# ManualBot_Shield.net
KiCad netlist of a schematic drawn in EAGLE
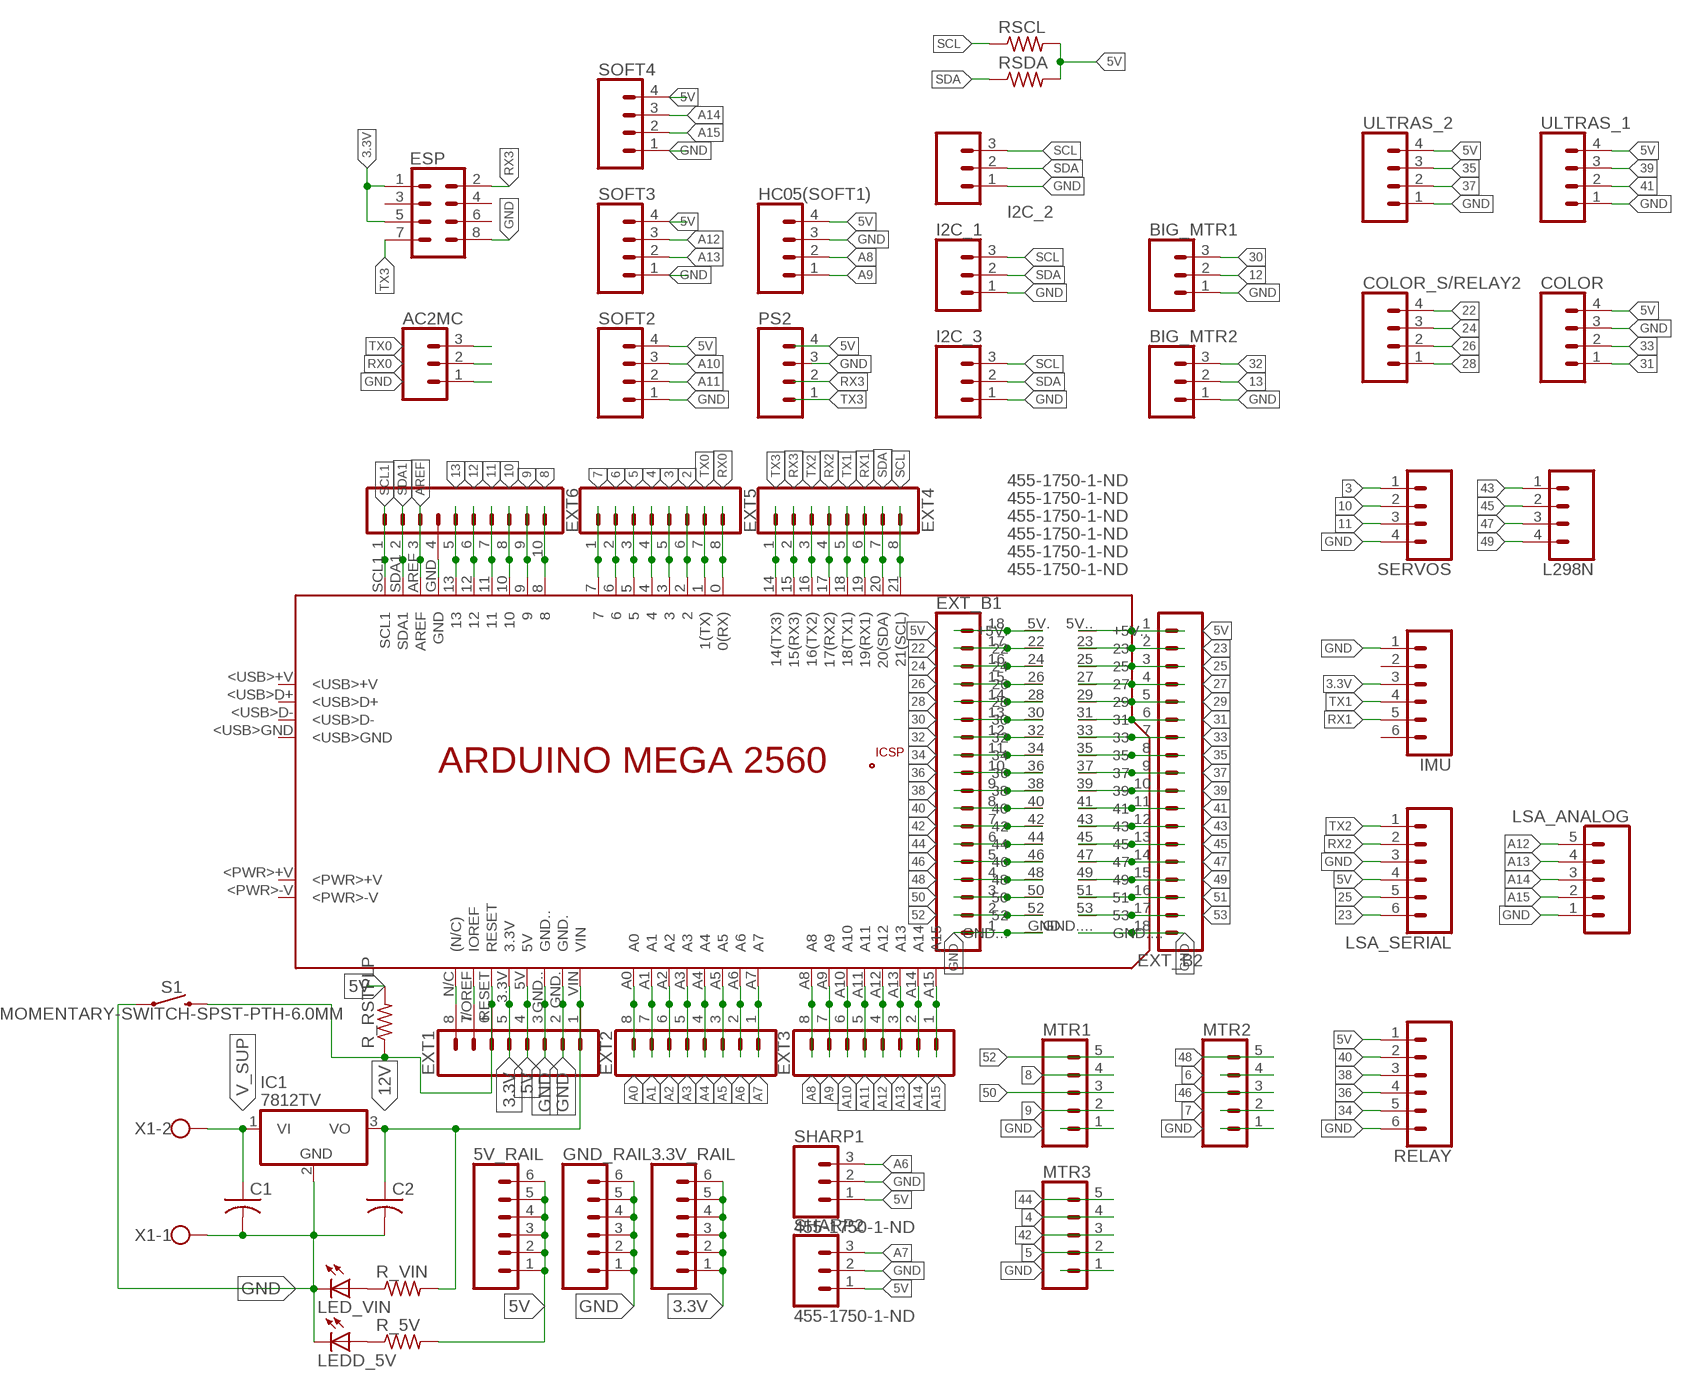
[diagram p0: schematic, sheet 1]

(export (version "E")
  (design (tool "Eeschema 10.0.6"))
  (components
    (comp (ref "3.3V_RAIL")
      (value "CONN_06SILK_FEMALE_PTH")
      (footprint "eagle-import:1X06")
      (libsource (lib "eagle-import") (part "CONN_06SILK_FEMALE_PTH"))
    )
    (comp (ref "5V_RAIL")
      (value "CONN_06SILK_FEMALE_PTH")
      (footprint "eagle-import:1X06")
      (libsource (lib "eagle-import") (part "CONN_06SILK_FEMALE_PTH"))
    )
    (comp (ref "AC2MC")
      (value "455-1750-1-ND")
      (footprint "eagle-import:1X03")
      (libsource (lib "eagle-import") (part "CONN_03"))
    )
    (comp (ref "BIG_MTR1")
      (value "455-1750-1-ND")
      (footprint "eagle-import:1X03")
      (libsource (lib "eagle-import") (part "CONN_03"))
    )
    (comp (ref "BIG_MTR2")
      (value "455-1750-1-ND")
      (footprint "eagle-import:1X03")
      (libsource (lib "eagle-import") (part "CONN_03"))
    )
    (comp (ref "C1")
      (value "C-US025-024X044")
      (footprint "eagle-import:C025-024X044")
      (libsource (lib "eagle-import") (part "C-US025-024X044"))
    )
    (comp (ref "C2")
      (value "C-US025-024X044")
      (footprint "eagle-import:C025-024X044")
      (libsource (lib "eagle-import") (part "C-US025-024X044"))
    )
    (comp (ref "COLOR")
      (value "CONN_04")
      (footprint "eagle-import:1X04")
      (libsource (lib "eagle-import") (part "CONN_04"))
    )
    (comp (ref "COLOR_S/RELAY2")
      (value "CONN_04")
      (footprint "eagle-import:1X04")
      (libsource (lib "eagle-import") (part "CONN_04"))
    )
    (comp (ref "ESP")
      (value "CONN_04X2")
      (footprint "eagle-import:2X4")
      (libsource (lib "eagle-import") (part "CONN_04X2"))
    )
    (comp (ref "EXT1")
      (value "CONN_08\"")
      (footprint "eagle-import:1X08")
      (libsource (lib "eagle-import") (part "CONN_08{dblquote}"))
    )
    (comp (ref "EXT2")
      (value "CONN_08\"")
      (footprint "eagle-import:1X08")
      (libsource (lib "eagle-import") (part "CONN_08{dblquote}"))
    )
    (comp (ref "EXT3")
      (value "CONN_08\"")
      (footprint "eagle-import:1X08")
      (libsource (lib "eagle-import") (part "CONN_08{dblquote}"))
    )
    (comp (ref "EXT4")
      (value "CONN_08\"")
      (footprint "eagle-import:1X08")
      (libsource (lib "eagle-import") (part "CONN_08{dblquote}"))
    )
    (comp (ref "EXT5")
      (value "CONN_08\"")
      (footprint "eagle-import:1X08")
      (libsource (lib "eagle-import") (part "CONN_08{dblquote}"))
    )
    (comp (ref "EXT6")
      (value "CONN_10\"")
      (footprint "eagle-import:1X10")
      (libsource (lib "eagle-import") (part "CONN_10{dblquote}"))
    )
    (comp (ref "EXT_B1")
      (value "CONN_18")
      (footprint "eagle-import:1X18_NO_SILK")
      (libsource (lib "eagle-import") (part "CONN_18"))
    )
    (comp (ref "EXT_B2")
      (value "CONN_18")
      (footprint "eagle-import:1X18_NO_SILK")
      (libsource (lib "eagle-import") (part "CONN_18"))
    )
    (comp (ref "GND_RAIL")
      (value "CONN_06SILK_FEMALE_PTH")
      (footprint "eagle-import:1X06")
      (libsource (lib "eagle-import") (part "CONN_06SILK_FEMALE_PTH"))
    )
    (comp (ref "HC05(SOFT1)")
      (value "CONN_04")
      (footprint "eagle-import:1X04")
      (libsource (lib "eagle-import") (part "CONN_04"))
    )
    (comp (ref "I2C_1")
      (value "455-1750-1-ND")
      (footprint "eagle-import:1X03")
      (libsource (lib "eagle-import") (part "CONN_03"))
    )
    (comp (ref "I2C_2")
      (value "455-1750-1-ND")
      (footprint "eagle-import:1X03")
      (libsource (lib "eagle-import") (part "CONN_03"))
    )
    (comp (ref "I2C_3")
      (value "455-1750-1-ND")
      (footprint "eagle-import:1X03")
      (libsource (lib "eagle-import") (part "CONN_03"))
    )
    (comp (ref "IC1")
      (value "7812TV")
      (footprint "eagle-import:TO220V")
      (libsource (lib "eagle-import") (part "78TV12"))
    )
    (comp (ref "IMU")
      (value "CONN_06SILK_FEMALE_PTH")
      (footprint "eagle-import:1X06")
      (libsource (lib "eagle-import") (part "CONN_06SILK_FEMALE_PTH"))
    )
    (comp (ref "L298N")
      (value "CONN_04")
      (footprint "eagle-import:1X04")
      (libsource (lib "eagle-import") (part "CONN_04"))
    )
    (comp (ref "LEDD_5V")
      (value "LED5MM")
      (footprint "eagle-import:LED5MM")
      (libsource (lib "eagle-import") (part "LED5MM"))
    )
    (comp (ref "LED_VIN")
      (value "LED5MM")
      (footprint "eagle-import:LED5MM")
      (libsource (lib "eagle-import") (part "LED5MM"))
    )
    (comp (ref "LSA_ANALOG")
      (value "CONN_05")
      (footprint "eagle-import:1X05")
      (libsource (lib "eagle-import") (part "CONN_05"))
    )
    (comp (ref "LSA_SERIAL")
      (value "CONN_06SILK_FEMALE_PTH")
      (footprint "eagle-import:1X06")
      (libsource (lib "eagle-import") (part "CONN_06SILK_FEMALE_PTH"))
    )
    (comp (ref "MTR1")
      (value "CONN_05")
      (footprint "eagle-import:1X05")
      (libsource (lib "eagle-import") (part "CONN_05"))
    )
    (comp (ref "MTR2")
      (value "CONN_05")
      (footprint "eagle-import:1X05")
      (libsource (lib "eagle-import") (part "CONN_05"))
    )
    (comp (ref "MTR3")
      (value "CONN_05")
      (footprint "eagle-import:1X05")
      (libsource (lib "eagle-import") (part "CONN_05"))
    )
    (comp (ref "PCB1")
      (value "ARDUINO_MEGA2560")
      (footprint "eagle-import:ARDUINO_MEGA2560")
      (libsource (lib "eagle-import") (part "ARDUINO_MEGA2560"))
    )
    (comp (ref "PS2")
      (value "CONN_04")
      (footprint "eagle-import:1X04")
      (libsource (lib "eagle-import") (part "CONN_04"))
    )
    (comp (ref "RELAY")
      (value "CONN_06SILK_FEMALE_PTH")
      (footprint "eagle-import:1X06")
      (libsource (lib "eagle-import") (part "CONN_06SILK_FEMALE_PTH"))
    )
    (comp (ref "RSCL")
      (value "R-US_0204/7")
      (footprint "eagle-import:0204_7")
      (libsource (lib "eagle-import") (part "R-US_0204/7"))
    )
    (comp (ref "RSDA")
      (value "R-US_0204/7")
      (footprint "eagle-import:0204_7")
      (libsource (lib "eagle-import") (part "R-US_0204/7"))
    )
    (comp (ref "R_5V")
      (value "R-US_0204/7")
      (footprint "eagle-import:0204_7")
      (libsource (lib "eagle-import") (part "R-US_0204/7"))
    )
    (comp (ref "R_RSTPLP")
      (value "R-US_0204/7")
      (footprint "eagle-import:0204_7")
      (libsource (lib "eagle-import") (part "R-US_0204/7"))
    )
    (comp (ref "R_VIN")
      (value "R-US_0204/7")
      (footprint "eagle-import:0204_7")
      (libsource (lib "eagle-import") (part "R-US_0204/7"))
    )
    (comp (ref "S1")
      (value "MOMENTARY-SWITCH-SPST-PTH-6.0MM")
      (footprint "eagle-import:TACTILE_SWITCH_PTH_6.0MM")
      (libsource (lib "eagle-import") (part "MOMENTARY-SWITCH-SPST-PTH-6.0MM"))
    )
    (comp (ref "SERVOS")
      (value "CONN_04")
      (footprint "eagle-import:1X04")
      (libsource (lib "eagle-import") (part "CONN_04"))
    )
    (comp (ref "SHARP1")
      (value "455-1750-1-ND")
      (footprint "eagle-import:1X03")
      (libsource (lib "eagle-import") (part "CONN_03"))
    )
    (comp (ref "SHARP2")
      (value "455-1750-1-ND")
      (footprint "eagle-import:1X03")
      (libsource (lib "eagle-import") (part "CONN_03"))
    )
    (comp (ref "SOFT2")
      (value "CONN_04")
      (footprint "eagle-import:1X04")
      (libsource (lib "eagle-import") (part "CONN_04"))
    )
    (comp (ref "SOFT3")
      (value "CONN_04")
      (footprint "eagle-import:1X04")
      (libsource (lib "eagle-import") (part "CONN_04"))
    )
    (comp (ref "SOFT4")
      (value "CONN_04")
      (footprint "eagle-import:1X04")
      (libsource (lib "eagle-import") (part "CONN_04"))
    )
    (comp (ref "ULTRAS_1")
      (value "CONN_04")
      (footprint "eagle-import:1X04")
      (libsource (lib "eagle-import") (part "CONN_04"))
    )
    (comp (ref "ULTRAS_2")
      (value "CONN_04")
      (footprint "eagle-import:1X04")
      (libsource (lib "eagle-import") (part "CONN_04"))
    )
    (comp (ref "X1")
      (value "W237-102")
      (footprint "eagle-import:W237-102")
      (fields (field (name "MPN") "237-102"))
      (libsource (lib "eagle-import") (part "W237-102"))
    )
  )
  (nets
    (net (code "1") (name "2") (class "Default")
      (node (ref "EXT5") (pin "6") (pinfunction "6_6") (pintype "passive"))
      (node (ref "PCB1") (pin "2") (pinfunction "2_2") (pintype "bidirectional"))
    )
    (net (code "2") (name "3") (class "Default")
      (node (ref "EXT5") (pin "5") (pinfunction "5_5") (pintype "passive"))
      (node (ref "PCB1") (pin "3") (pinfunction "3_3") (pintype "bidirectional"))
      (node (ref "SERVOS") (pin "1") (pinfunction "1_1") (pintype "passive"))
    )
    (net (code "3") (name "3.3V") (class "Default")
      (node (ref "3.3V_RAIL") (pin "1") (pinfunction "1_1") (pintype "passive"))
      (node (ref "3.3V_RAIL") (pin "2") (pinfunction "2_2") (pintype "passive"))
      (node (ref "3.3V_RAIL") (pin "3") (pinfunction "3_3") (pintype "passive"))
      (node (ref "3.3V_RAIL") (pin "4") (pinfunction "4_4") (pintype "passive"))
      (node (ref "3.3V_RAIL") (pin "5") (pinfunction "5_5") (pintype "passive"))
      (node (ref "3.3V_RAIL") (pin "6") (pinfunction "6_6") (pintype "passive"))
      (node (ref "ESP") (pin "1") (pinfunction "1_1") (pintype "passive"))
      (node (ref "ESP") (pin "5") (pinfunction "5_5") (pintype "passive"))
      (node (ref "EXT1") (pin "5") (pinfunction "5_5") (pintype "passive"))
      (node (ref "IMU") (pin "3") (pinfunction "3_3") (pintype "passive"))
      (node (ref "PCB1") (pin "3.3V") (pinfunction "3.3V_3.3V") (pintype "bidirectional"))
    )
    (net (code "4") (name "4") (class "Default")
      (node (ref "EXT5") (pin "4") (pinfunction "4_4") (pintype "passive"))
      (node (ref "MTR3") (pin "4") (pinfunction "4_4") (pintype "passive"))
      (node (ref "PCB1") (pin "4") (pinfunction "4_4") (pintype "bidirectional"))
    )
    (net (code "5") (name "5") (class "Default")
      (node (ref "EXT5") (pin "3") (pinfunction "3_3") (pintype "passive"))
      (node (ref "MTR3") (pin "2") (pinfunction "2_2") (pintype "passive"))
      (node (ref "PCB1") (pin "5") (pinfunction "5_5") (pintype "bidirectional"))
    )
    (net (code "6") (name "5V") (class "Default")
      (node (ref "5V_RAIL") (pin "1") (pinfunction "1_1") (pintype "passive"))
      (node (ref "5V_RAIL") (pin "2") (pinfunction "2_2") (pintype "passive"))
      (node (ref "5V_RAIL") (pin "3") (pinfunction "3_3") (pintype "passive"))
      (node (ref "5V_RAIL") (pin "4") (pinfunction "4_4") (pintype "passive"))
      (node (ref "5V_RAIL") (pin "5") (pinfunction "5_5") (pintype "passive"))
      (node (ref "5V_RAIL") (pin "6") (pinfunction "6_6") (pintype "passive"))
      (node (ref "COLOR") (pin "4") (pinfunction "4_4") (pintype "passive"))
      (node (ref "EXT1") (pin "4") (pinfunction "4_4") (pintype "passive"))
      (node (ref "EXT_B1") (pin "18") (pinfunction "18_18") (pintype "passive"))
      (node (ref "EXT_B2") (pin "1") (pinfunction "1_1") (pintype "passive"))
      (node (ref "HC05(SOFT1)") (pin "4") (pinfunction "4_4") (pintype "passive"))
      (node (ref "LSA_SERIAL") (pin "4") (pinfunction "4_4") (pintype "passive"))
      (node (ref "PCB1") (pin "5V") (pinfunction "5V_5V") (pintype "bidirectional"))
      (node (ref "PCB1") (pin "5V.") (pinfunction "+5V._5V.") (pintype "bidirectional"))
      (node (ref "PCB1") (pin "5V..") (pinfunction "+5V.._5V..") (pintype "bidirectional"))
      (node (ref "PS2") (pin "4") (pinfunction "4_4") (pintype "passive"))
      (node (ref "RELAY") (pin "1") (pinfunction "1_1") (pintype "passive"))
      (node (ref "RSCL") (pin "2") (pinfunction "2_2") (pintype "passive"))
      (node (ref "RSDA") (pin "2") (pinfunction "2_2") (pintype "passive"))
      (node (ref "R_5V") (pin "2") (pinfunction "2_2") (pintype "passive"))
      (node (ref "R_RSTPLP") (pin "2") (pinfunction "2_2") (pintype "passive"))
      (node (ref "SHARP1") (pin "1") (pinfunction "1_1") (pintype "passive"))
      (node (ref "SHARP2") (pin "1") (pinfunction "1_1") (pintype "passive"))
      (node (ref "SOFT2") (pin "4") (pinfunction "4_4") (pintype "passive"))
      (node (ref "SOFT3") (pin "4") (pinfunction "4_4") (pintype "passive"))
      (node (ref "SOFT4") (pin "4") (pinfunction "4_4") (pintype "passive"))
      (node (ref "ULTRAS_1") (pin "4") (pinfunction "4_4") (pintype "passive"))
      (node (ref "ULTRAS_2") (pin "4") (pinfunction "4_4") (pintype "passive"))
    )
    (net (code "7") (name "6") (class "Default")
      (node (ref "EXT5") (pin "2") (pinfunction "2_2") (pintype "passive"))
      (node (ref "MTR2") (pin "4") (pinfunction "4_4") (pintype "passive"))
      (node (ref "PCB1") (pin "6") (pinfunction "6_6") (pintype "bidirectional"))
    )
    (net (code "8") (name "7") (class "Default")
      (node (ref "EXT5") (pin "1") (pinfunction "1_1") (pintype "passive"))
      (node (ref "MTR2") (pin "2") (pinfunction "2_2") (pintype "passive"))
      (node (ref "PCB1") (pin "7") (pinfunction "7_7") (pintype "bidirectional"))
    )
    (net (code "9") (name "8") (class "Default")
      (node (ref "EXT6") (pin "10") (pinfunction "10_10") (pintype "passive"))
      (node (ref "MTR1") (pin "4") (pinfunction "4_4") (pintype "passive"))
      (node (ref "PCB1") (pin "8") (pinfunction "8_8") (pintype "bidirectional"))
    )
    (net (code "10") (name "9") (class "Default")
      (node (ref "EXT6") (pin "9") (pinfunction "9_9") (pintype "passive"))
      (node (ref "MTR1") (pin "2") (pinfunction "2_2") (pintype "passive"))
      (node (ref "PCB1") (pin "9") (pinfunction "9_9") (pintype "bidirectional"))
    )
    (net (code "11") (name "10") (class "Default")
      (node (ref "EXT6") (pin "8") (pinfunction "8_8") (pintype "passive"))
      (node (ref "PCB1") (pin "10") (pinfunction "10_10") (pintype "bidirectional"))
      (node (ref "SERVOS") (pin "2") (pinfunction "2_2") (pintype "passive"))
    )
    (net (code "12") (name "11") (class "Default")
      (node (ref "EXT6") (pin "7") (pinfunction "7_7") (pintype "passive"))
      (node (ref "PCB1") (pin "11") (pinfunction "11_11") (pintype "bidirectional"))
      (node (ref "SERVOS") (pin "3") (pinfunction "3_3") (pintype "passive"))
    )
    (net (code "13") (name "12") (class "Default")
      (node (ref "BIG_MTR1") (pin "2") (pinfunction "2_2") (pintype "passive"))
      (node (ref "EXT6") (pin "6") (pinfunction "6_6") (pintype "passive"))
      (node (ref "PCB1") (pin "12") (pinfunction "12_12") (pintype "bidirectional"))
    )
    (net (code "14") (name "12V") (class "Default")
      (node (ref "C2") (pin "1") (pinfunction "1_1") (pintype "passive"))
      (node (ref "EXT1") (pin "1") (pinfunction "1_1") (pintype "passive"))
      (node (ref "IC1") (pin "3") (pinfunction "VO_3") (pintype "passive"))
      (node (ref "PCB1") (pin "VIN") (pinfunction "VIN_VIN") (pintype "bidirectional"))
      (node (ref "R_VIN") (pin "2") (pinfunction "2_2") (pintype "passive"))
    )
    (net (code "15") (name "13") (class "Default")
      (node (ref "BIG_MTR2") (pin "2") (pinfunction "2_2") (pintype "passive"))
      (node (ref "EXT6") (pin "5") (pinfunction "5_5") (pintype "passive"))
      (node (ref "PCB1") (pin "13") (pinfunction "13_13") (pintype "bidirectional"))
    )
    (net (code "16") (name "22") (class "Default")
      (node (ref "COLOR_S/RELAY2") (pin "4") (pinfunction "4_4") (pintype "passive"))
      (node (ref "EXT_B1") (pin "17") (pinfunction "17_17") (pintype "passive"))
      (node (ref "PCB1") (pin "22") (pinfunction "22_22") (pintype "bidirectional"))
    )
    (net (code "17") (name "23") (class "Default")
      (node (ref "EXT_B2") (pin "2") (pinfunction "2_2") (pintype "passive"))
      (node (ref "LSA_SERIAL") (pin "6") (pinfunction "6_6") (pintype "passive"))
      (node (ref "PCB1") (pin "23") (pinfunction "23_23") (pintype "bidirectional"))
    )
    (net (code "18") (name "24") (class "Default")
      (node (ref "COLOR_S/RELAY2") (pin "3") (pinfunction "3_3") (pintype "passive"))
      (node (ref "EXT_B1") (pin "16") (pinfunction "16_16") (pintype "passive"))
      (node (ref "PCB1") (pin "24") (pinfunction "24_24") (pintype "bidirectional"))
    )
    (net (code "19") (name "25") (class "Default")
      (node (ref "EXT_B2") (pin "3") (pinfunction "3_3") (pintype "passive"))
      (node (ref "LSA_SERIAL") (pin "5") (pinfunction "5_5") (pintype "passive"))
      (node (ref "PCB1") (pin "25") (pinfunction "25_25") (pintype "bidirectional"))
    )
    (net (code "20") (name "26") (class "Default")
      (node (ref "COLOR_S/RELAY2") (pin "2") (pinfunction "2_2") (pintype "passive"))
      (node (ref "EXT_B1") (pin "15") (pinfunction "15_15") (pintype "passive"))
      (node (ref "PCB1") (pin "26") (pinfunction "26_26") (pintype "bidirectional"))
    )
    (net (code "21") (name "27") (class "Default")
      (node (ref "EXT_B2") (pin "4") (pinfunction "4_4") (pintype "passive"))
      (node (ref "PCB1") (pin "27") (pinfunction "27_27") (pintype "bidirectional"))
    )
    (net (code "22") (name "28") (class "Default")
      (node (ref "COLOR_S/RELAY2") (pin "1") (pinfunction "1_1") (pintype "passive"))
      (node (ref "EXT_B1") (pin "14") (pinfunction "14_14") (pintype "passive"))
      (node (ref "PCB1") (pin "28") (pinfunction "28_28") (pintype "bidirectional"))
    )
    (net (code "23") (name "29") (class "Default")
      (node (ref "EXT_B2") (pin "5") (pinfunction "5_5") (pintype "passive"))
      (node (ref "PCB1") (pin "29") (pinfunction "29_29") (pintype "bidirectional"))
    )
    (net (code "24") (name "30") (class "Default")
      (node (ref "BIG_MTR1") (pin "3") (pinfunction "3_3") (pintype "passive"))
      (node (ref "EXT_B1") (pin "13") (pinfunction "13_13") (pintype "passive"))
      (node (ref "PCB1") (pin "30") (pinfunction "30_30") (pintype "bidirectional"))
    )
    (net (code "25") (name "31") (class "Default")
      (node (ref "COLOR") (pin "1") (pinfunction "1_1") (pintype "passive"))
      (node (ref "EXT_B2") (pin "6") (pinfunction "6_6") (pintype "passive"))
      (node (ref "PCB1") (pin "31") (pinfunction "31_31") (pintype "bidirectional"))
    )
    (net (code "26") (name "32") (class "Default")
      (node (ref "BIG_MTR2") (pin "3") (pinfunction "3_3") (pintype "passive"))
      (node (ref "EXT_B1") (pin "12") (pinfunction "12_12") (pintype "passive"))
      (node (ref "PCB1") (pin "32") (pinfunction "32_32") (pintype "bidirectional"))
    )
    (net (code "27") (name "33") (class "Default")
      (node (ref "COLOR") (pin "2") (pinfunction "2_2") (pintype "passive"))
      (node (ref "EXT_B2") (pin "7") (pinfunction "7_7") (pintype "passive"))
      (node (ref "PCB1") (pin "33") (pinfunction "33_33") (pintype "bidirectional"))
    )
    (net (code "28") (name "34") (class "Default")
      (node (ref "EXT_B1") (pin "11") (pinfunction "11_11") (pintype "passive"))
      (node (ref "PCB1") (pin "34") (pinfunction "34_34") (pintype "bidirectional"))
      (node (ref "RELAY") (pin "5") (pinfunction "5_5") (pintype "passive"))
    )
    (net (code "29") (name "35") (class "Default")
      (node (ref "EXT_B2") (pin "8") (pinfunction "8_8") (pintype "passive"))
      (node (ref "PCB1") (pin "35") (pinfunction "35_35") (pintype "bidirectional"))
      (node (ref "ULTRAS_2") (pin "3") (pinfunction "3_3") (pintype "passive"))
    )
    (net (code "30") (name "36") (class "Default")
      (node (ref "EXT_B1") (pin "10") (pinfunction "10_10") (pintype "passive"))
      (node (ref "PCB1") (pin "36") (pinfunction "36_36") (pintype "bidirectional"))
      (node (ref "RELAY") (pin "4") (pinfunction "4_4") (pintype "passive"))
    )
    (net (code "31") (name "37") (class "Default")
      (node (ref "EXT_B2") (pin "9") (pinfunction "9_9") (pintype "passive"))
      (node (ref "PCB1") (pin "37") (pinfunction "37_37") (pintype "bidirectional"))
      (node (ref "ULTRAS_2") (pin "2") (pinfunction "2_2") (pintype "passive"))
    )
    (net (code "32") (name "38") (class "Default")
      (node (ref "EXT_B1") (pin "9") (pinfunction "9_9") (pintype "passive"))
      (node (ref "PCB1") (pin "38") (pinfunction "38_38") (pintype "bidirectional"))
      (node (ref "RELAY") (pin "3") (pinfunction "3_3") (pintype "passive"))
    )
    (net (code "33") (name "39") (class "Default")
      (node (ref "EXT_B2") (pin "10") (pinfunction "10_10") (pintype "passive"))
      (node (ref "PCB1") (pin "39") (pinfunction "39_39") (pintype "bidirectional"))
      (node (ref "ULTRAS_1") (pin "3") (pinfunction "3_3") (pintype "passive"))
    )
    (net (code "34") (name "40") (class "Default")
      (node (ref "EXT_B1") (pin "8") (pinfunction "8_8") (pintype "passive"))
      (node (ref "PCB1") (pin "40") (pinfunction "40_40") (pintype "bidirectional"))
      (node (ref "RELAY") (pin "2") (pinfunction "2_2") (pintype "passive"))
    )
    (net (code "35") (name "41") (class "Default")
      (node (ref "EXT_B2") (pin "11") (pinfunction "11_11") (pintype "passive"))
      (node (ref "PCB1") (pin "41") (pinfunction "41_41") (pintype "bidirectional"))
      (node (ref "ULTRAS_1") (pin "2") (pinfunction "2_2") (pintype "passive"))
    )
    (net (code "36") (name "42") (class "Default")
      (node (ref "EXT_B1") (pin "7") (pinfunction "7_7") (pintype "passive"))
      (node (ref "MTR3") (pin "3") (pinfunction "3_3") (pintype "passive"))
      (node (ref "PCB1") (pin "42") (pinfunction "42_42") (pintype "bidirectional"))
    )
    (net (code "37") (name "43") (class "Default")
      (node (ref "EXT_B2") (pin "12") (pinfunction "12_12") (pintype "passive"))
      (node (ref "L298N") (pin "1") (pinfunction "1_1") (pintype "passive"))
      (node (ref "PCB1") (pin "43") (pinfunction "43_43") (pintype "bidirectional"))
    )
    (net (code "38") (name "44") (class "Default")
      (node (ref "EXT_B1") (pin "6") (pinfunction "6_6") (pintype "passive"))
      (node (ref "MTR3") (pin "5") (pinfunction "5_5") (pintype "passive"))
      (node (ref "PCB1") (pin "44") (pinfunction "44_44") (pintype "bidirectional"))
    )
    (net (code "39") (name "45") (class "Default")
      (node (ref "EXT_B2") (pin "13") (pinfunction "13_13") (pintype "passive"))
      (node (ref "L298N") (pin "2") (pinfunction "2_2") (pintype "passive"))
      (node (ref "PCB1") (pin "45") (pinfunction "45_45") (pintype "bidirectional"))
    )
    (net (code "40") (name "46") (class "Default")
      (node (ref "EXT_B1") (pin "5") (pinfunction "5_5") (pintype "passive"))
      (node (ref "MTR2") (pin "3") (pinfunction "3_3") (pintype "passive"))
      (node (ref "PCB1") (pin "46") (pinfunction "46_46") (pintype "bidirectional"))
    )
    (net (code "41") (name "47") (class "Default")
      (node (ref "EXT_B2") (pin "14") (pinfunction "14_14") (pintype "passive"))
      (node (ref "L298N") (pin "3") (pinfunction "3_3") (pintype "passive"))
      (node (ref "PCB1") (pin "47") (pinfunction "47_47") (pintype "bidirectional"))
    )
    (net (code "42") (name "48") (class "Default")
      (node (ref "EXT_B1") (pin "4") (pinfunction "4_4") (pintype "passive"))
      (node (ref "MTR2") (pin "5") (pinfunction "5_5") (pintype "passive"))
      (node (ref "PCB1") (pin "48") (pinfunction "48_48") (pintype "bidirectional"))
    )
    (net (code "43") (name "49") (class "Default")
      (node (ref "EXT_B2") (pin "15") (pinfunction "15_15") (pintype "passive"))
      (node (ref "L298N") (pin "4") (pinfunction "4_4") (pintype "passive"))
      (node (ref "PCB1") (pin "49") (pinfunction "49_49") (pintype "bidirectional"))
    )
    (net (code "44") (name "50") (class "Default")
      (node (ref "EXT_B1") (pin "3") (pinfunction "3_3") (pintype "passive"))
      (node (ref "MTR1") (pin "3") (pinfunction "3_3") (pintype "passive"))
      (node (ref "PCB1") (pin "50") (pinfunction "50_50") (pintype "bidirectional"))
    )
    (net (code "45") (name "51") (class "Default")
      (node (ref "EXT_B2") (pin "16") (pinfunction "16_16") (pintype "passive"))
      (node (ref "PCB1") (pin "51") (pinfunction "51_51") (pintype "bidirectional"))
    )
    (net (code "46") (name "52") (class "Default")
      (node (ref "EXT_B1") (pin "2") (pinfunction "2_2") (pintype "passive"))
      (node (ref "MTR1") (pin "5") (pinfunction "5_5") (pintype "passive"))
      (node (ref "PCB1") (pin "52") (pinfunction "52_52") (pintype "bidirectional"))
    )
    (net (code "47") (name "53") (class "Default")
      (node (ref "EXT_B2") (pin "17") (pinfunction "17_17") (pintype "passive"))
      (node (ref "PCB1") (pin "53") (pinfunction "53_53") (pintype "bidirectional"))
    )
    (net (code "48") (name "A0") (class "Default")
      (node (ref "EXT2") (pin "8") (pinfunction "8_8") (pintype "passive"))
      (node (ref "PCB1") (pin "A0") (pinfunction "A0_A0") (pintype "bidirectional"))
    )
    (net (code "49") (name "A1") (class "Default")
      (node (ref "EXT2") (pin "7") (pinfunction "7_7") (pintype "passive"))
      (node (ref "PCB1") (pin "A1") (pinfunction "A1_A1") (pintype "bidirectional"))
    )
    (net (code "50") (name "A2") (class "Default")
      (node (ref "EXT2") (pin "6") (pinfunction "6_6") (pintype "passive"))
      (node (ref "PCB1") (pin "A2") (pinfunction "A2_A2") (pintype "bidirectional"))
    )
    (net (code "51") (name "A3") (class "Default")
      (node (ref "EXT2") (pin "5") (pinfunction "5_5") (pintype "passive"))
      (node (ref "PCB1") (pin "A3") (pinfunction "A3_A3") (pintype "bidirectional"))
    )
    (net (code "52") (name "A4") (class "Default")
      (node (ref "EXT2") (pin "4") (pinfunction "4_4") (pintype "passive"))
      (node (ref "PCB1") (pin "A4") (pinfunction "A4_A4") (pintype "bidirectional"))
    )
    (net (code "53") (name "A5") (class "Default")
      (node (ref "EXT2") (pin "3") (pinfunction "3_3") (pintype "passive"))
      (node (ref "PCB1") (pin "A5") (pinfunction "A5_A5") (pintype "bidirectional"))
    )
    (net (code "54") (name "A6") (class "Default")
      (node (ref "EXT2") (pin "2") (pinfunction "2_2") (pintype "passive"))
      (node (ref "PCB1") (pin "A6") (pinfunction "A6_A6") (pintype "bidirectional"))
      (node (ref "SHARP1") (pin "3") (pinfunction "3_3") (pintype "passive"))
    )
    (net (code "55") (name "A7") (class "Default")
      (node (ref "EXT2") (pin "1") (pinfunction "1_1") (pintype "passive"))
      (node (ref "PCB1") (pin "A7") (pinfunction "A7_A7") (pintype "bidirectional"))
      (node (ref "SHARP2") (pin "3") (pinfunction "3_3") (pintype "passive"))
    )
    (net (code "56") (name "A8") (class "Default")
      (node (ref "EXT3") (pin "8") (pinfunction "8_8") (pintype "passive"))
      (node (ref "HC05(SOFT1)") (pin "2") (pinfunction "2_2") (pintype "passive"))
      (node (ref "PCB1") (pin "A8") (pinfunction "A8_A8") (pintype "bidirectional"))
    )
    (net (code "57") (name "A9") (class "Default")
      (node (ref "EXT3") (pin "7") (pinfunction "7_7") (pintype "passive"))
      (node (ref "HC05(SOFT1)") (pin "1") (pinfunction "1_1") (pintype "passive"))
      (node (ref "PCB1") (pin "A9") (pinfunction "A9_A9") (pintype "bidirectional"))
    )
    (net (code "58") (name "A10") (class "Default")
      (node (ref "EXT3") (pin "6") (pinfunction "6_6") (pintype "passive"))
      (node (ref "PCB1") (pin "A10") (pinfunction "A10_A10") (pintype "bidirectional"))
      (node (ref "SOFT2") (pin "3") (pinfunction "3_3") (pintype "passive"))
    )
    (net (code "59") (name "A11") (class "Default")
      (node (ref "EXT3") (pin "5") (pinfunction "5_5") (pintype "passive"))
      (node (ref "PCB1") (pin "A11") (pinfunction "A11_A11") (pintype "bidirectional"))
      (node (ref "SOFT2") (pin "2") (pinfunction "2_2") (pintype "passive"))
    )
    (net (code "60") (name "A12") (class "Default")
      (node (ref "EXT3") (pin "4") (pinfunction "4_4") (pintype "passive"))
      (node (ref "LSA_ANALOG") (pin "5") (pinfunction "5_5") (pintype "passive"))
      (node (ref "PCB1") (pin "A12") (pinfunction "A12_A12") (pintype "bidirectional"))
      (node (ref "SOFT3") (pin "3") (pinfunction "3_3") (pintype "passive"))
    )
    (net (code "61") (name "A13") (class "Default")
      (node (ref "EXT3") (pin "3") (pinfunction "3_3") (pintype "passive"))
      (node (ref "LSA_ANALOG") (pin "4") (pinfunction "4_4") (pintype "passive"))
      (node (ref "PCB1") (pin "A13") (pinfunction "A13_A13") (pintype "bidirectional"))
      (node (ref "SOFT3") (pin "2") (pinfunction "2_2") (pintype "passive"))
    )
    (net (code "62") (name "A14") (class "Default")
      (node (ref "EXT3") (pin "2") (pinfunction "2_2") (pintype "passive"))
      (node (ref "LSA_ANALOG") (pin "3") (pinfunction "3_3") (pintype "passive"))
      (node (ref "PCB1") (pin "A14") (pinfunction "A14_A14") (pintype "bidirectional"))
      (node (ref "SOFT4") (pin "3") (pinfunction "3_3") (pintype "passive"))
    )
    (net (code "63") (name "A15") (class "Default")
      (node (ref "EXT3") (pin "1") (pinfunction "1_1") (pintype "passive"))
      (node (ref "LSA_ANALOG") (pin "2") (pinfunction "2_2") (pintype "passive"))
      (node (ref "PCB1") (pin "A15") (pinfunction "A15_A15") (pintype "bidirectional"))
      (node (ref "SOFT4") (pin "2") (pinfunction "2_2") (pintype "passive"))
    )
    (net (code "64") (name "AREF") (class "Default")
      (node (ref "EXT6") (pin "3") (pinfunction "3_3") (pintype "passive"))
      (node (ref "PCB1") (pin "AREF") (pinfunction "AREF_AREF") (pintype "bidirectional"))
    )
    (net (code "65") (name "GND") (class "Default")
      (node (ref "AC2MC") (pin "1") (pinfunction "1_1") (pintype "passive"))
      (node (ref "BIG_MTR1") (pin "1") (pinfunction "1_1") (pintype "passive"))
      (node (ref "BIG_MTR2") (pin "1") (pinfunction "1_1") (pintype "passive"))
      (node (ref "C1") (pin "2") (pinfunction "2_2") (pintype "passive"))
      (node (ref "C2") (pin "2") (pinfunction "2_2") (pintype "passive"))
      (node (ref "COLOR") (pin "3") (pinfunction "3_3") (pintype "passive"))
      (node (ref "ESP") (pin "8") (pinfunction "8_8") (pintype "passive"))
      (node (ref "EXT1") (pin "2") (pinfunction "2_2") (pintype "passive"))
      (node (ref "EXT1") (pin "3") (pinfunction "3_3") (pintype "passive"))
      (node (ref "EXT6") (pin "4") (pinfunction "4_4") (pintype "passive"))
      (node (ref "EXT_B1") (pin "1") (pinfunction "1_1") (pintype "passive"))
      (node (ref "EXT_B2") (pin "18") (pinfunction "18_18") (pintype "passive"))
      (node (ref "GND_RAIL") (pin "1") (pinfunction "1_1") (pintype "passive"))
      (node (ref "GND_RAIL") (pin "2") (pinfunction "2_2") (pintype "passive"))
      (node (ref "GND_RAIL") (pin "3") (pinfunction "3_3") (pintype "passive"))
      (node (ref "GND_RAIL") (pin "4") (pinfunction "4_4") (pintype "passive"))
      (node (ref "GND_RAIL") (pin "5") (pinfunction "5_5") (pintype "passive"))
      (node (ref "GND_RAIL") (pin "6") (pinfunction "6_6") (pintype "passive"))
      (node (ref "HC05(SOFT1)") (pin "3") (pinfunction "3_3") (pintype "passive"))
      (node (ref "I2C_1") (pin "1") (pinfunction "1_1") (pintype "passive"))
      (node (ref "I2C_2") (pin "1") (pinfunction "1_1") (pintype "passive"))
      (node (ref "I2C_3") (pin "1") (pinfunction "1_1") (pintype "passive"))
      (node (ref "IC1") (pin "2") (pinfunction "GND_2") (pintype "passive"))
      (node (ref "IMU") (pin "1") (pinfunction "1_1") (pintype "passive"))
      (node (ref "LEDD_5V") (pin "K") (pinfunction "C_K") (pintype "passive"))
      (node (ref "LED_VIN") (pin "K") (pinfunction "C_K") (pintype "passive"))
      (node (ref "LSA_ANALOG") (pin "1") (pinfunction "1_1") (pintype "passive"))
      (node (ref "LSA_SERIAL") (pin "3") (pinfunction "3_3") (pintype "passive"))
      (node (ref "MTR1") (pin "1") (pinfunction "1_1") (pintype "passive"))
      (node (ref "MTR2") (pin "1") (pinfunction "1_1") (pintype "passive"))
      (node (ref "MTR3") (pin "1") (pinfunction "1_1") (pintype "passive"))
      (node (ref "PCB1") (pin "GND") (pinfunction "GND_GND") (pintype "bidirectional"))
      (node (ref "PCB1") (pin "GND.") (pinfunction "GND._GND.") (pintype "bidirectional"))
      (node (ref "PCB1") (pin "GND..") (pinfunction "GND.._GND..") (pintype "bidirectional"))
      (node (ref "PCB1") (pin "GND...") (pinfunction "GND..._GND...") (pintype "bidirectional"))
      (node (ref "PCB1") (pin "GND....") (pinfunction "GND...._GND....") (pintype "bidirectional"))
      (node (ref "PS2") (pin "3") (pinfunction "3_3") (pintype "passive"))
      (node (ref "RELAY") (pin "6") (pinfunction "6_6") (pintype "passive"))
      (node (ref "S1") (pin "1") (pinfunction "1_1") (pintype "passive"))
      (node (ref "SERVOS") (pin "4") (pinfunction "4_4") (pintype "passive"))
      (node (ref "SHARP1") (pin "2") (pinfunction "2_2") (pintype "passive"))
      (node (ref "SHARP2") (pin "2") (pinfunction "2_2") (pintype "passive"))
      (node (ref "SOFT2") (pin "1") (pinfunction "1_1") (pintype "passive"))
      (node (ref "SOFT3") (pin "1") (pinfunction "1_1") (pintype "passive"))
      (node (ref "SOFT4") (pin "1") (pinfunction "1_1") (pintype "passive"))
      (node (ref "ULTRAS_1") (pin "1") (pinfunction "1_1") (pintype "passive"))
      (node (ref "ULTRAS_2") (pin "1") (pinfunction "1_1") (pintype "passive"))
      (node (ref "X1") (pin "1") (pinfunction "KL_1") (pintype "passive"))
    )
    (net (code "66") (name "Net-(LEDD_5V-PadA)") (class "Default")
      (node (ref "LEDD_5V") (pin "A") (pinfunction "A_A") (pintype "passive"))
      (node (ref "R_5V") (pin "1") (pinfunction "1_1") (pintype "passive"))
    )
    (net (code "67") (name "Net-(LED_VIN-PadA)") (class "Default")
      (node (ref "LED_VIN") (pin "A") (pinfunction "A_A") (pintype "passive"))
      (node (ref "R_VIN") (pin "1") (pinfunction "1_1") (pintype "passive"))
    )
    (net (code "68") (name "Net-(PCB1-(N{slash}C))") (class "Default")
      (node (ref "EXT1") (pin "8") (pinfunction "8_8") (pintype "passive"))
      (node (ref "PCB1") (pin "N/C") (pinfunction "(N/C)_N/C") (pintype "bidirectional"))
    )
    (net (code "69") (name "Net-(PCB1-IOREF)") (class "Default")
      (node (ref "EXT1") (pin "7") (pinfunction "7_7") (pintype "passive"))
      (node (ref "PCB1") (pin "I/OREF") (pinfunction "IOREF_I/OREF") (pintype "bidirectional"))
    )
    (net (code "70") (name "Net-(S1-2)") (class "Default")
      (node (ref "EXT1") (pin "6") (pinfunction "6_6") (pintype "passive"))
      (node (ref "PCB1") (pin "RESET") (pinfunction "RESET_RESET") (pintype "bidirectional"))
      (node (ref "R_RSTPLP") (pin "1") (pinfunction "1_1") (pintype "passive"))
      (node (ref "S1") (pin "3") (pinfunction "2_3") (pintype "passive"))
    )
    (net (code "71") (name "RX0") (class "Default")
      (node (ref "AC2MC") (pin "2") (pinfunction "2_2") (pintype "passive"))
      (node (ref "EXT5") (pin "8") (pinfunction "8_8") (pintype "passive"))
      (node (ref "PCB1") (pin "0") (pinfunction "0(RX)_0") (pintype "bidirectional"))
    )
    (net (code "72") (name "RX1") (class "Default")
      (node (ref "EXT4") (pin "6") (pinfunction "6_6") (pintype "passive"))
      (node (ref "IMU") (pin "5") (pinfunction "5_5") (pintype "passive"))
      (node (ref "PCB1") (pin "19") (pinfunction "19(RX1)_19") (pintype "bidirectional"))
    )
    (net (code "73") (name "RX2") (class "Default")
      (node (ref "EXT4") (pin "4") (pinfunction "4_4") (pintype "passive"))
      (node (ref "LSA_SERIAL") (pin "2") (pinfunction "2_2") (pintype "passive"))
      (node (ref "PCB1") (pin "17") (pinfunction "17(RX2)_17") (pintype "bidirectional"))
    )
    (net (code "74") (name "RX3") (class "Default")
      (node (ref "ESP") (pin "2") (pinfunction "2_2") (pintype "passive"))
      (node (ref "EXT4") (pin "2") (pinfunction "2_2") (pintype "passive"))
      (node (ref "PCB1") (pin "15") (pinfunction "15(RX3)_15") (pintype "bidirectional"))
      (node (ref "PS2") (pin "2") (pinfunction "2_2") (pintype "passive"))
    )
    (net (code "75") (name "SCL") (class "Default")
      (node (ref "EXT4") (pin "8") (pinfunction "8_8") (pintype "passive"))
      (node (ref "I2C_1") (pin "3") (pinfunction "3_3") (pintype "passive"))
      (node (ref "I2C_2") (pin "3") (pinfunction "3_3") (pintype "passive"))
      (node (ref "I2C_3") (pin "3") (pinfunction "3_3") (pintype "passive"))
      (node (ref "PCB1") (pin "21") (pinfunction "21(SCL)_21") (pintype "bidirectional"))
      (node (ref "RSCL") (pin "1") (pinfunction "1_1") (pintype "passive"))
    )
    (net (code "76") (name "SCL1") (class "Default")
      (node (ref "EXT6") (pin "1") (pinfunction "1_1") (pintype "passive"))
      (node (ref "PCB1") (pin "SCL1") (pinfunction "SCL1_SCL1") (pintype "bidirectional"))
    )
    (net (code "77") (name "SDA") (class "Default")
      (node (ref "EXT4") (pin "7") (pinfunction "7_7") (pintype "passive"))
      (node (ref "I2C_1") (pin "2") (pinfunction "2_2") (pintype "passive"))
      (node (ref "I2C_2") (pin "2") (pinfunction "2_2") (pintype "passive"))
      (node (ref "I2C_3") (pin "2") (pinfunction "2_2") (pintype "passive"))
      (node (ref "PCB1") (pin "20") (pinfunction "20(SDA)_20") (pintype "bidirectional"))
      (node (ref "RSDA") (pin "1") (pinfunction "1_1") (pintype "passive"))
    )
    (net (code "78") (name "SDA1") (class "Default")
      (node (ref "EXT6") (pin "2") (pinfunction "2_2") (pintype "passive"))
      (node (ref "PCB1") (pin "SDA1") (pinfunction "SDA1_SDA1") (pintype "bidirectional"))
    )
    (net (code "79") (name "TX0") (class "Default")
      (node (ref "AC2MC") (pin "3") (pinfunction "3_3") (pintype "passive"))
      (node (ref "EXT5") (pin "7") (pinfunction "7_7") (pintype "passive"))
      (node (ref "PCB1") (pin "1") (pinfunction "1(TX)_1") (pintype "bidirectional"))
    )
    (net (code "80") (name "TX1") (class "Default")
      (node (ref "EXT4") (pin "5") (pinfunction "5_5") (pintype "passive"))
      (node (ref "IMU") (pin "4") (pinfunction "4_4") (pintype "passive"))
      (node (ref "PCB1") (pin "18") (pinfunction "18(TX1)_18") (pintype "bidirectional"))
    )
    (net (code "81") (name "TX2") (class "Default")
      (node (ref "EXT4") (pin "3") (pinfunction "3_3") (pintype "passive"))
      (node (ref "LSA_SERIAL") (pin "1") (pinfunction "1_1") (pintype "passive"))
      (node (ref "PCB1") (pin "16") (pinfunction "16(TX2)_16") (pintype "bidirectional"))
    )
    (net (code "82") (name "TX3") (class "Default")
      (node (ref "ESP") (pin "7") (pinfunction "7_7") (pintype "passive"))
      (node (ref "EXT4") (pin "1") (pinfunction "1_1") (pintype "passive"))
      (node (ref "PCB1") (pin "14") (pinfunction "14(TX3)_14") (pintype "bidirectional"))
      (node (ref "PS2") (pin "1") (pinfunction "1_1") (pintype "passive"))
    )
    (net (code "83") (name "V_SUP") (class "Default")
      (node (ref "C1") (pin "1") (pinfunction "1_1") (pintype "passive"))
      (node (ref "IC1") (pin "1") (pinfunction "VI_1") (pintype "input"))
      (node (ref "X1") (pin "2") (pinfunction "KL_2") (pintype "passive"))
    )
    (net (code "84") (name "unconnected-(ESP-Pad3)") (class "Default")
      (node (ref "ESP") (pin "3") (pinfunction "3_3") (pintype "passive"))
    )
    (net (code "85") (name "unconnected-(ESP-Pad4)") (class "Default")
      (node (ref "ESP") (pin "4") (pinfunction "4_4") (pintype "passive"))
    )
    (net (code "86") (name "unconnected-(ESP-Pad6)") (class "Default")
      (node (ref "ESP") (pin "6") (pinfunction "6_6") (pintype "passive"))
    )
    (net (code "87") (name "unconnected-(IMU-Pad2)") (class "Default")
      (node (ref "IMU") (pin "2") (pinfunction "2_2") (pintype "passive"))
    )
    (net (code "88") (name "unconnected-(IMU-Pad6)") (class "Default")
      (node (ref "IMU") (pin "6") (pinfunction "6_6") (pintype "passive"))
    )
    (net (code "89") (name "unconnected-(PCB1-Pad+5V_)") (class "Default")
      (node (ref "PCB1") (pin "+5V_") (pinfunction "+5V__+5V_") (pintype "bidirectional"))
    )
    (net (code "90") (name "unconnected-(PCB1-Pad<PWR>+V)") (class "Default")
      (node (ref "PCB1") (pin "<PWR>+V") (pinfunction "<PWR>+V_<PWR>+V") (pintype "no_connect"))
    )
    (net (code "91") (name "unconnected-(PCB1-Pad<PWR>-V)") (class "Default")
      (node (ref "PCB1") (pin "<PWR>-V") (pinfunction "<PWR>-V_<PWR>-V") (pintype "no_connect"))
    )
    (net (code "92") (name "unconnected-(PCB1-Pad<USB>+V)") (class "Default")
      (node (ref "PCB1") (pin "<USB>+V") (pinfunction "<USB>+V_<USB>+V") (pintype "no_connect"))
    )
    (net (code "93") (name "unconnected-(PCB1-Pad<USB>D+)") (class "Default")
      (node (ref "PCB1") (pin "<USB>D+") (pinfunction "<USB>D+_<USB>D+") (pintype "no_connect"))
    )
    (net (code "94") (name "unconnected-(PCB1-Pad<USB>D-)") (class "Default")
      (node (ref "PCB1") (pin "<USB>D-") (pinfunction "<USB>D-_<USB>D-") (pintype "no_connect"))
    )
    (net (code "95") (name "unconnected-(PCB1-Pad<USB>GND)") (class "Default")
      (node (ref "PCB1") (pin "<USB>GND") (pinfunction "<USB>GND_<USB>GND") (pintype "no_connect"))
    )
    (net (code "96") (name "unconnected-(PCB1-PadGND__)") (class "Default")
      (node (ref "PCB1") (pin "GND__") (pinfunction "GND___GND__") (pintype "bidirectional"))
    )
    (net (code "97") (name "unconnected-(PCB1-PadMISO)") (class "Default")
      (node (ref "PCB1") (pin "MISO") (pinfunction "MISO_MISO") (pintype "bidirectional"))
    )
    (net (code "98") (name "unconnected-(PCB1-PadMOSI)") (class "Default")
      (node (ref "PCB1") (pin "MOSI") (pinfunction "MOSI_MOSI") (pintype "bidirectional"))
    )
    (net (code "99") (name "unconnected-(PCB1-PadRESET.)") (class "Default")
      (node (ref "PCB1") (pin "RESET.") (pinfunction "RESET._RESET.") (pintype "bidirectional"))
    )
    (net (code "100") (name "unconnected-(PCB1-PadSCK)") (class "Default")
      (node (ref "PCB1") (pin "SCK") (pinfunction "SCK_SCK") (pintype "bidirectional"))
    )
  )
)
